# LEDDimmerI2C_RevB.net
KiCad netlist of a schematic drawn in EAGLE
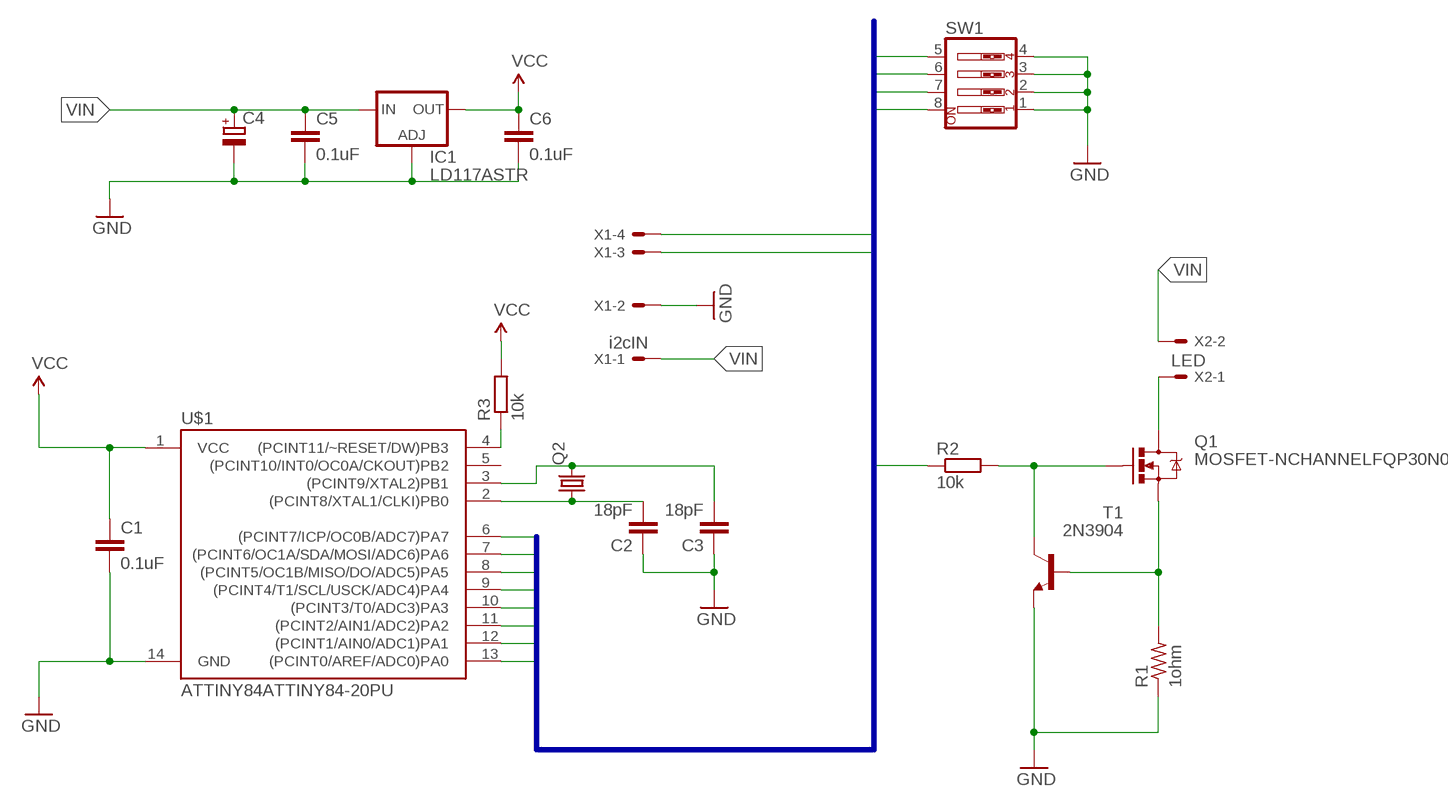
[diagram p0: schematic, sheet 1]

(export (version "E")
  (design (tool "Eeschema 10.0.6"))
  (components
    (comp (ref "C1")
      (value "0.1uF")
      (footprint "eagle-import:0805")
      (libsource (lib "eagle-import") (part "CAP0805"))
    )
    (comp (ref "C2")
      (value "18pF")
      (footprint "eagle-import:0805")
      (libsource (lib "eagle-import") (part "CAP0805"))
    )
    (comp (ref "C3")
      (value "18pF")
      (footprint "eagle-import:0805")
      (libsource (lib "eagle-import") (part "CAP0805"))
    )
    (comp (ref "C4")
      (value "CPOL-EUE3.5-10")
      (footprint "eagle-import:E3,5-10")
      (libsource (lib "eagle-import") (part "CPOL-EUE3.5-10"))
    )
    (comp (ref "C5")
      (value "0.1uF")
      (footprint "eagle-import:0805")
      (libsource (lib "eagle-import") (part "CAP0805"))
    )
    (comp (ref "C6")
      (value "0.1uF")
      (footprint "eagle-import:0805")
      (libsource (lib "eagle-import") (part "CAP0805"))
    )
    (comp (ref "IC1")
      (value "LD117ASTR")
      (footprint "eagle-import:SOT223")
      (libsource (lib "eagle-import") (part "LD117A?STR"))
    )
    (comp (ref "Q1")
      (value "MOSFET-NCHANNELFQP30N06L")
      (footprint "eagle-import:TO220V")
      (libsource (lib "eagle-import") (part "MOSFET-NCHANNELFQP30N06L"))
    )
    (comp (ref "Q2")
      (value "CRYSTALSM49")
      (footprint "eagle-import:SM49")
      (libsource (lib "eagle-import") (part "CRYSTALSM49"))
    )
    (comp (ref "R1")
      (value "1ohm")
      (footprint "eagle-import:VTA54")
      (libsource (lib "eagle-import") (part "R-US_VTA54"))
    )
    (comp (ref "R2")
      (value "10k")
      (footprint "eagle-import:R0805")
      (libsource (lib "eagle-import") (part "R-EU_R0805"))
    )
    (comp (ref "R3")
      (value "10k")
      (footprint "eagle-import:R0805")
      (libsource (lib "eagle-import") (part "R-EU_R0805"))
    )
    (comp (ref "SW1")
      (value "SW_DIP-4")
      (footprint "eagle-import:EDG-04")
      (libsource (lib "eagle-import") (part "SW_DIP-4"))
    )
    (comp (ref "T1")
      (value "2N3904")
      (footprint "eagle-import:TO92")
      (libsource (lib "eagle-import") (part "2N3904"))
    )
    (comp (ref "U$1")
      (value "ATTINY84ATTINY84-20PU")
      (footprint "eagle-import:DIL14")
      (libsource (lib "eagle-import") (part "ATTINY84ATTINY84-20PU"))
    )
    (comp (ref "X1")
      (value "i2cIN")
      (footprint "eagle-import:22-23-2041")
      (fields (field (name "MF") "MOLEX") (field (name "MPN") "22-23-2041"))
      (libsource (lib "eagle-import") (part "22-23-2041"))
    )
    (comp (ref "X2")
      (value "LED")
      (footprint "eagle-import:22-23-2021")
      (fields (field (name "MF") "MOLEX") (field (name "MPN") "22-23-2021"))
      (libsource (lib "eagle-import") (part "22-23-2021"))
    )
  )
  (nets
    (net (code "1") (name "/PORTA0") (class "Default")
      (node (ref "SW1") (pin "5") (pinfunction "5_5") (pintype "passive"))
      (node (ref "U$1") (pin "13") (pinfunction "(PCINT0/AREF/ADC0)PA0_13") (pintype "bidirectional"))
    )
    (net (code "2") (name "/PORTA1") (class "Default")
      (node (ref "SW1") (pin "6") (pinfunction "6_6") (pintype "passive"))
      (node (ref "U$1") (pin "12") (pinfunction "(PCINT1/AIN0/ADC1)PA1_12") (pintype "bidirectional"))
    )
    (net (code "3") (name "/PORTA2") (class "Default")
      (node (ref "SW1") (pin "7") (pinfunction "7_7") (pintype "passive"))
      (node (ref "U$1") (pin "11") (pinfunction "(PCINT2/AIN1/ADC2)PA2_11") (pintype "bidirectional"))
    )
    (net (code "4") (name "/PORTA3") (class "Default")
      (node (ref "SW1") (pin "8") (pinfunction "8_8") (pintype "passive"))
      (node (ref "U$1") (pin "10") (pinfunction "(PCINT3/T0/ADC3)PA3_10") (pintype "bidirectional"))
    )
    (net (code "5") (name "/PORTA4") (class "Default")
      (node (ref "U$1") (pin "9") (pinfunction "(PCINT4/T1/SCL/USCK/ADC4)PA4_9") (pintype "bidirectional"))
      (node (ref "X1") (pin "4") (pinfunction "S_4") (pintype "passive"))
    )
    (net (code "6") (name "/PORTA5") (class "Default")
      (node (ref "R2") (pin "1") (pinfunction "1_1") (pintype "passive"))
      (node (ref "U$1") (pin "8") (pinfunction "(PCINT5/OC1B/MISO/DO/ADC5)PA5_8") (pintype "bidirectional"))
    )
    (net (code "7") (name "/PORTA6") (class "Default")
      (node (ref "U$1") (pin "7") (pinfunction "(PCINT6/OC1A/SDA/MOSI/ADC6)PA6_7") (pintype "bidirectional"))
      (node (ref "X1") (pin "3") (pinfunction "S_3") (pintype "passive"))
    )
    (net (code "8") (name "GND") (class "Default")
      (node (ref "C1") (pin "2") (pinfunction "2_2") (pintype "passive"))
      (node (ref "C2") (pin "1") (pinfunction "1_1") (pintype "passive"))
      (node (ref "C3") (pin "1") (pinfunction "1_1") (pintype "passive"))
      (node (ref "C4") (pin "-") (pinfunction "-_-") (pintype "passive"))
      (node (ref "C5") (pin "2") (pinfunction "2_2") (pintype "passive"))
      (node (ref "C6") (pin "2") (pinfunction "2_2") (pintype "passive"))
      (node (ref "IC1") (pin "1") (pinfunction "ADJ_1") (pintype "input"))
      (node (ref "R1") (pin "1") (pinfunction "1_1") (pintype "passive"))
      (node (ref "SW1") (pin "1") (pinfunction "1_1") (pintype "passive"))
      (node (ref "SW1") (pin "2") (pinfunction "2_2") (pintype "passive"))
      (node (ref "SW1") (pin "3") (pinfunction "3_3") (pintype "passive"))
      (node (ref "SW1") (pin "4") (pinfunction "4_4") (pintype "passive"))
      (node (ref "T1") (pin "3") (pinfunction "E_3") (pintype "passive"))
      (node (ref "U$1") (pin "14") (pinfunction "GND_14") (pintype "bidirectional"))
      (node (ref "X1") (pin "2") (pinfunction "S_2") (pintype "passive"))
    )
    (net (code "9") (name "Net-(Q1-D)") (class "Default")
      (node (ref "Q1") (pin "2") (pinfunction "D_2") (pintype "passive"))
      (node (ref "X2") (pin "1") (pinfunction "S_1") (pintype "passive"))
    )
    (net (code "10") (name "Net-(Q1-G)") (class "Default")
      (node (ref "Q1") (pin "1") (pinfunction "G_1") (pintype "passive"))
      (node (ref "R2") (pin "2") (pinfunction "2_2") (pintype "passive"))
      (node (ref "T1") (pin "1") (pinfunction "C_1") (pintype "passive"))
    )
    (net (code "11") (name "Net-(Q1-S)") (class "Default")
      (node (ref "Q1") (pin "3") (pinfunction "S_3") (pintype "passive"))
      (node (ref "R1") (pin "2") (pinfunction "2_2") (pintype "passive"))
      (node (ref "T1") (pin "2") (pinfunction "B_2") (pintype "passive"))
    )
    (net (code "12") (name "Net-(U$1-(PCINT8{slash}XTAL1{slash}CLKI)PB0)") (class "Default")
      (node (ref "C2") (pin "2") (pinfunction "2_2") (pintype "passive"))
      (node (ref "Q2") (pin "1") (pinfunction "1_1") (pintype "passive"))
      (node (ref "U$1") (pin "2") (pinfunction "(PCINT8/XTAL1/CLKI)PB0_2") (pintype "bidirectional"))
    )
    (net (code "13") (name "Net-(U$1-(PCINT9{slash}XTAL2)PB1)") (class "Default")
      (node (ref "C3") (pin "2") (pinfunction "2_2") (pintype "passive"))
      (node (ref "Q2") (pin "2") (pinfunction "2_2") (pintype "passive"))
      (node (ref "U$1") (pin "3") (pinfunction "(PCINT9/XTAL2)PB1_3") (pintype "bidirectional"))
    )
    (net (code "14") (name "Net-(U$1-(PCINT11{slash}~{RESET{slash}DW})PB3)") (class "Default")
      (node (ref "R3") (pin "1") (pinfunction "1_1") (pintype "passive"))
      (node (ref "U$1") (pin "4") (pinfunction "(PCINT11/~{RESET/DW})PB3_4") (pintype "bidirectional"))
    )
    (net (code "15") (name "VCC") (class "Default")
      (node (ref "C1") (pin "1") (pinfunction "1_1") (pintype "passive"))
      (node (ref "C6") (pin "1") (pinfunction "1_1") (pintype "passive"))
      (node (ref "IC1") (pin "4") (pinfunction "OUT_4") (pintype "passive"))
      (node (ref "R3") (pin "2") (pinfunction "2_2") (pintype "passive"))
      (node (ref "U$1") (pin "1") (pinfunction "VCC_1") (pintype "bidirectional"))
    )
    (net (code "16") (name "VIN") (class "Default")
      (node (ref "C4") (pin "+") (pinfunction "+_+") (pintype "passive"))
      (node (ref "C5") (pin "1") (pinfunction "1_1") (pintype "passive"))
      (node (ref "IC1") (pin "3") (pinfunction "IN_3") (pintype "input"))
      (node (ref "X1") (pin "1") (pinfunction "S_1") (pintype "passive"))
      (node (ref "X2") (pin "2") (pinfunction "S_2") (pintype "passive"))
    )
    (net (code "17") (name "unconnected-(U$1-(PCINT7{slash}ICP{slash}OC0B{slash}ADC7)PA7-Pad6)") (class "Default")
      (node (ref "U$1") (pin "6") (pinfunction "(PCINT7/ICP/OC0B/ADC7)PA7_6") (pintype "bidirectional"))
    )
    (net (code "18") (name "unconnected-(U$1-(PCINT10{slash}INT0{slash}OC0A{slash}CKOUT)PB2-Pad5)") (class "Default")
      (node (ref "U$1") (pin "5") (pinfunction "(PCINT10/INT0/OC0A/CKOUT)PB2_5") (pintype "bidirectional"))
    )
  )
)
